# BPF.net
KiCad netlist of a schematic drawn in Altium Designer
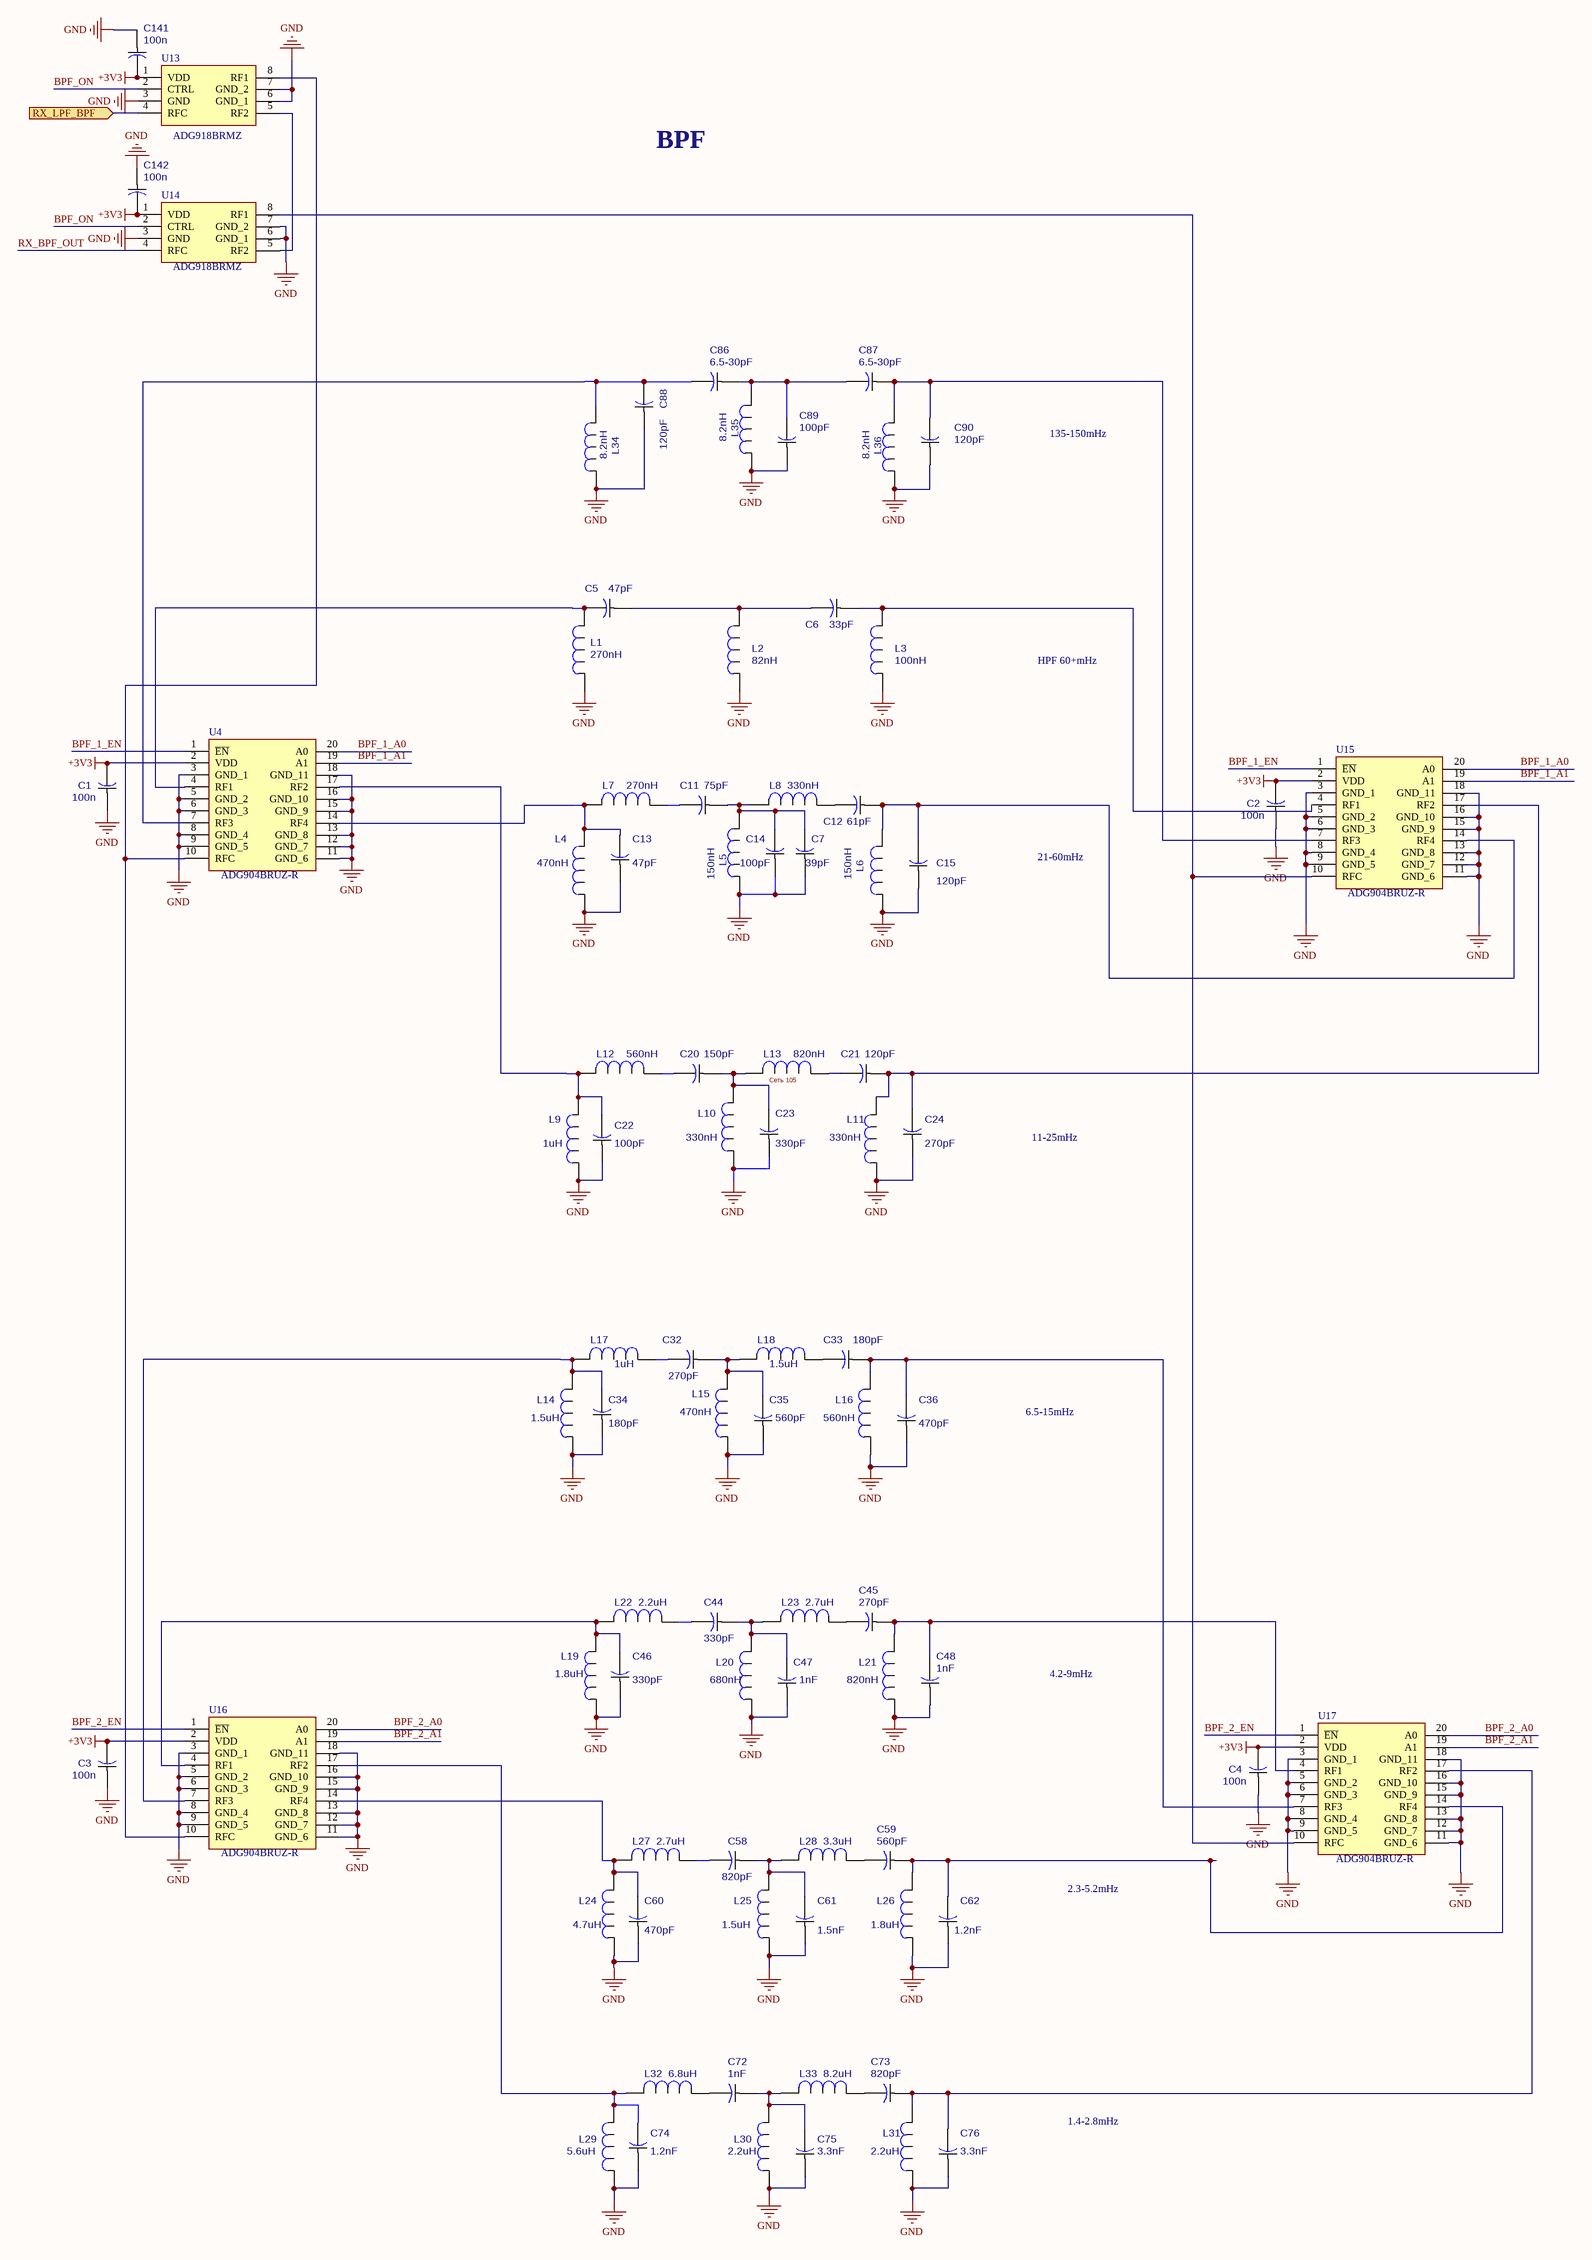
[diagram p0: BPF.SchDoc]

(export (version "E")
  (design (tool "Eeschema 10.0.6"))
  (components
    (comp (ref "C1")
      (value "100n")
      (footprint "CAP_0805")
      (description "CAP_0805")
      (libsource (lib "*") (part "CAP_0805"))
    )
    (comp (ref "C2")
      (value "100n")
      (footprint "CAP_0805")
      (description "CAP_0805")
      (libsource (lib "*") (part "CAP_0805"))
    )
    (comp (ref "C3")
      (value "100n")
      (footprint "CAP_0805")
      (description "CAP_0805")
      (libsource (lib "*") (part "CAP_0805"))
    )
    (comp (ref "C4")
      (value "100n")
      (footprint "CAP_0805")
      (description "CAP_0805")
      (libsource (lib "*") (part "CAP_0805"))
    )
    (comp (ref "C5")
      (value "47pF")
      (footprint "CAP_0805")
      (description "CAP_0805")
      (libsource (lib "*") (part "CAP_0805"))
    )
    (comp (ref "C6")
      (value "33pF")
      (footprint "CAP_0805")
      (description "CAP_0805")
      (libsource (lib "*") (part "CAP_0805"))
    )
    (comp (ref "C7")
      (value "39pF")
      (footprint "CAP_0805")
      (description "CAP_0805")
      (libsource (lib "*") (part "CAP_0805"))
    )
    (comp (ref "C11")
      (value "75pF")
      (footprint "CAP_0805")
      (description "CAP_0805")
      (libsource (lib "*") (part "CAP_0805"))
    )
    (comp (ref "C12")
      (value "61pF")
      (footprint "CAP_0805")
      (description "CAP_0805")
      (libsource (lib "*") (part "CAP_0805"))
    )
    (comp (ref "C13")
      (value "47pF")
      (footprint "CAP_0805")
      (description "CAP_0805")
      (libsource (lib "*") (part "CAP_0805"))
    )
    (comp (ref "C14")
      (value "100pF")
      (footprint "CAP_0805")
      (description "CAP_0805")
      (libsource (lib "*") (part "CAP_0805"))
    )
    (comp (ref "C15")
      (value "120pF")
      (footprint "CAP_0805")
      (description "CAP_0805")
      (libsource (lib "*") (part "CAP_0805"))
    )
    (comp (ref "C20")
      (value "150pF")
      (footprint "CAP_0805")
      (description "CAP_0805")
      (libsource (lib "*") (part "CAP_0805"))
    )
    (comp (ref "C21")
      (value "120pF")
      (footprint "CAP_0805")
      (description "CAP_0805")
      (libsource (lib "*") (part "CAP_0805"))
    )
    (comp (ref "C22")
      (value "100pF")
      (footprint "CAP_0805")
      (description "CAP_0805")
      (libsource (lib "*") (part "CAP_0805"))
    )
    (comp (ref "C23")
      (value "330pF")
      (footprint "CAP_0805")
      (description "CAP_0805")
      (libsource (lib "*") (part "CAP_0805"))
    )
    (comp (ref "C24")
      (value "270pF")
      (footprint "CAP_0805")
      (description "CAP_0805")
      (libsource (lib "*") (part "CAP_0805"))
    )
    (comp (ref "C32")
      (value "270pF")
      (footprint "CAP_0805")
      (description "CAP_0805")
      (libsource (lib "*") (part "CAP_0805"))
    )
    (comp (ref "C33")
      (value "180pF")
      (footprint "CAP_0805")
      (description "CAP_0805")
      (libsource (lib "*") (part "CAP_0805"))
    )
    (comp (ref "C34")
      (value "180pF")
      (footprint "CAP_0805")
      (description "CAP_0805")
      (libsource (lib "*") (part "CAP_0805"))
    )
    (comp (ref "C35")
      (value "560pF")
      (footprint "CAP_0805")
      (description "CAP_0805")
      (libsource (lib "*") (part "CAP_0805"))
    )
    (comp (ref "C36")
      (value "470pF")
      (footprint "CAP_0805")
      (description "CAP_0805")
      (libsource (lib "*") (part "CAP_0805"))
    )
    (comp (ref "C44")
      (value "330pF")
      (footprint "CAP_0805")
      (description "CAP_0805")
      (libsource (lib "*") (part "CAP_0805"))
    )
    (comp (ref "C45")
      (value "270pF")
      (footprint "CAP_0805")
      (description "CAP_0805")
      (fields (field (name "Comment") "51pF"))
      (libsource (lib "*") (part "CAP_0805"))
    )
    (comp (ref "C46")
      (value "330pF")
      (footprint "CAP_0805")
      (description "CAP_0805")
      (libsource (lib "*") (part "CAP_0805"))
    )
    (comp (ref "C47")
      (value "1nF")
      (footprint "CAP_0805")
      (description "CAP_0805")
      (libsource (lib "*") (part "CAP_0805"))
    )
    (comp (ref "C48")
      (value "1nF")
      (footprint "CAP_0805")
      (description "CAP_0805")
      (libsource (lib "*") (part "CAP_0805"))
    )
    (comp (ref "C58")
      (value "820pF")
      (footprint "CAP_0805")
      (description "CAP_0805")
      (libsource (lib "*") (part "CAP_0805"))
    )
    (comp (ref "C59")
      (value "560pF")
      (footprint "CAP_0805")
      (description "CAP_0805")
      (fields (field (name "Comment") "680pF"))
      (libsource (lib "*") (part "CAP_0805"))
    )
    (comp (ref "C60")
      (value "470pF")
      (footprint "CAP_0805")
      (description "CAP_0805")
      (libsource (lib "*") (part "CAP_0805"))
    )
    (comp (ref "C61")
      (value "1.5nF")
      (footprint "CAP_0805")
      (description "CAP_0805")
      (libsource (lib "*") (part "CAP_0805"))
    )
    (comp (ref "C62")
      (value "1.2nF")
      (footprint "CAP_0805")
      (description "CAP_0805")
      (libsource (lib "*") (part "CAP_0805"))
    )
    (comp (ref "C72")
      (value "1nF")
      (footprint "CAP_0805")
      (description "CAP_0805")
      (libsource (lib "*") (part "CAP_0805"))
    )
    (comp (ref "C73")
      (value "820pF")
      (footprint "CAP_0805")
      (description "CAP_0805")
      (libsource (lib "*") (part "CAP_0805"))
    )
    (comp (ref "C74")
      (value "1.2nF")
      (footprint "CAP_0805")
      (description "CAP_0805")
      (libsource (lib "*") (part "CAP_0805"))
    )
    (comp (ref "C75")
      (value "3.3nF")
      (footprint "CAP_0805")
      (description "CAP_0805")
      (libsource (lib "*") (part "CAP_0805"))
    )
    (comp (ref "C76")
      (value "3.3nF")
      (footprint "CAP_0805")
      (description "CAP_0805")
      (libsource (lib "*") (part "CAP_0805"))
    )
    (comp (ref "C86")
      (value "6.5-30pF")
      (footprint "5025[2010]")
      (description "TZC3P300A110")
      (libsource (lib "*") (part "CAP_0805"))
    )
    (comp (ref "C87")
      (value "6.5-30pF")
      (footprint "5025[2010]")
      (description "TZC3P300A110")
      (libsource (lib "*") (part "CAP_0805"))
    )
    (comp (ref "C88")
      (value "120pF")
      (footprint "CAP_0805")
      (description "CAP_0805")
      (libsource (lib "*") (part "CAP_0805"))
    )
    (comp (ref "C89")
      (value "100pF")
      (footprint "CAP_0805")
      (description "CAP_0805")
      (libsource (lib "*") (part "CAP_0805"))
    )
    (comp (ref "C90")
      (value "120pF")
      (footprint "CAP_0805")
      (description "CAP_0805")
      (libsource (lib "*") (part "CAP_0805"))
    )
    (comp (ref "C141")
      (value "100n")
      (footprint "CAP_0805")
      (description "CAP_0805")
      (libsource (lib "*") (part "CAP_0805"))
    )
    (comp (ref "C142")
      (value "100n")
      (footprint "CAP_0805")
      (description "CAP_0805")
      (libsource (lib "*") (part "CAP_0805"))
    )
    (comp (ref "L1")
      (value "270nH")
      (footprint "IND_0805")
      (description "IND_0805")
      (libsource (lib "*") (part "IND_0805"))
    )
    (comp (ref "L2")
      (value "82nH")
      (footprint "IND_0805")
      (description "IND_0805")
      (libsource (lib "*") (part "IND_0805"))
    )
    (comp (ref "L3")
      (value "100nH")
      (footprint "IND_0805")
      (description "IND_0805")
      (libsource (lib "*") (part "IND_0805"))
    )
    (comp (ref "L4")
      (value "470nH")
      (footprint "IND_0805")
      (description "IND_0805")
      (libsource (lib "*") (part "IND_0805"))
    )
    (comp (ref "L5")
      (value "150nH")
      (footprint "IND_0805")
      (description "IND_0805")
      (libsource (lib "*") (part "IND_0805"))
    )
    (comp (ref "L6")
      (value "150nH")
      (footprint "IND_0805")
      (description "IND_0805")
      (libsource (lib "*") (part "IND_0805"))
    )
    (comp (ref "L7")
      (value "270nH")
      (footprint "IND_0805")
      (description "IND_0805")
      (libsource (lib "*") (part "IND_0805"))
    )
    (comp (ref "L8")
      (value "330nH")
      (footprint "IND_0805")
      (description "IND_0805")
      (libsource (lib "*") (part "IND_0805"))
    )
    (comp (ref "L9")
      (value "1uH")
      (footprint "IND_0805")
      (description "IND_0805")
      (libsource (lib "*") (part "IND_0805"))
    )
    (comp (ref "L10")
      (value "330nH")
      (footprint "IND_0805")
      (description "IND_0805")
      (libsource (lib "*") (part "IND_0805"))
    )
    (comp (ref "L11")
      (value "330nH")
      (footprint "IND_0805")
      (description "IND_0805")
      (libsource (lib "*") (part "IND_0805"))
    )
    (comp (ref "L12")
      (value "560nH")
      (footprint "IND_0805")
      (description "IND_0805")
      (libsource (lib "*") (part "IND_0805"))
    )
    (comp (ref "L13")
      (value "820nH")
      (footprint "IND_0805")
      (description "IND_0805")
      (libsource (lib "*") (part "IND_0805"))
    )
    (comp (ref "L14")
      (value "1.5uH")
      (footprint "IND_0805")
      (description "IND_0805")
      (libsource (lib "*") (part "IND_0805"))
    )
    (comp (ref "L15")
      (value "470nH")
      (footprint "IND_0805")
      (description "IND_0805")
      (libsource (lib "*") (part "IND_0805"))
    )
    (comp (ref "L16")
      (value "560nH")
      (footprint "IND_0805")
      (description "IND_0805")
      (libsource (lib "*") (part "IND_0805"))
    )
    (comp (ref "L17")
      (value "1uH")
      (footprint "IND_0805")
      (description "IND_0805")
      (libsource (lib "*") (part "IND_0805"))
    )
    (comp (ref "L18")
      (value "1.5uH")
      (footprint "IND_0805")
      (description "IND_0805")
      (libsource (lib "*") (part "IND_0805"))
    )
    (comp (ref "L19")
      (value "1.8uH")
      (footprint "IND_0805")
      (description "IND_0805")
      (libsource (lib "*") (part "IND_0805"))
    )
    (comp (ref "L20")
      (value "680nH")
      (footprint "IND_0805")
      (description "IND_0805")
      (libsource (lib "*") (part "IND_0805"))
    )
    (comp (ref "L21")
      (value "820nH")
      (footprint "IND_0805")
      (description "IND_0805")
      (libsource (lib "*") (part "IND_0805"))
    )
    (comp (ref "L22")
      (value "2.2uH")
      (footprint "IND_0805")
      (description "IND_0805")
      (libsource (lib "*") (part "IND_0805"))
    )
    (comp (ref "L23")
      (value "2.7uH")
      (footprint "IND_0805")
      (description "IND_0805")
      (libsource (lib "*") (part "IND_0805"))
    )
    (comp (ref "L24")
      (value "4.7uH")
      (footprint "IND_0805")
      (description "IND_0805")
      (libsource (lib "*") (part "IND_0805"))
    )
    (comp (ref "L25")
      (value "1.5uH")
      (footprint "IND_0805")
      (description "IND_0805")
      (libsource (lib "*") (part "IND_0805"))
    )
    (comp (ref "L26")
      (value "1.8uH")
      (footprint "IND_0805")
      (description "IND_0805")
      (libsource (lib "*") (part "IND_0805"))
    )
    (comp (ref "L27")
      (value "2.7uH")
      (footprint "IND_0805")
      (description "IND_0805")
      (libsource (lib "*") (part "IND_0805"))
    )
    (comp (ref "L28")
      (value "3.3uH")
      (footprint "IND_0805")
      (description "IND_0805")
      (libsource (lib "*") (part "IND_0805"))
    )
    (comp (ref "L29")
      (value "5.6uH")
      (footprint "IND_0805")
      (description "IND_0805")
      (libsource (lib "*") (part "IND_0805"))
    )
    (comp (ref "L30")
      (value "2.2uH")
      (footprint "IND_0805")
      (description "IND_0805")
      (libsource (lib "*") (part "IND_0805"))
    )
    (comp (ref "L31")
      (value "2.2uH")
      (footprint "IND_0805")
      (description "IND_0805")
      (libsource (lib "*") (part "IND_0805"))
    )
    (comp (ref "L32")
      (value "6.8uH")
      (footprint "IND_0805")
      (description "IND_0805")
      (libsource (lib "*") (part "IND_0805"))
    )
    (comp (ref "L33")
      (value "8.2uH")
      (footprint "IND_0805")
      (description "IND_0805")
      (libsource (lib "*") (part "IND_0805"))
    )
    (comp (ref "L34")
      (value "8.2nH")
      (footprint "IND_0805")
      (description "IND_0805")
      (libsource (lib "*") (part "IND_0805"))
    )
    (comp (ref "L35")
      (value "8.2nH")
      (footprint "IND_0805")
      (description "IND_0805")
      (libsource (lib "*") (part "IND_0805"))
    )
    (comp (ref "L36")
      (value "8.2nH")
      (footprint "IND_0805")
      (description "IND_0805")
      (libsource (lib "*") (part "IND_0805"))
    )
    (comp (ref "U4")
      (value "ADG904BRUZ-R")
      (footprint "SamacSys:SOP65P640X120-20N")
      (description "Integrated Circuit")
      (fields
        (field (name "MOUSER PART NUMBER") "584-ADG904BRUZ-R")
        (field (name "RS PART NUMBER") "5385019P")
      )
      (libsource (lib "*") (part "ADG904BRUZ-R"))
    )
    (comp (ref "U13")
      (value "ADG918BRMZ")
      (footprint "SamacSys:SOP65P490X110-8N")
      (description "Integrated Circuit")
      (fields (field (name "MOUSER PART NUMBER") "584-ADG918BRMZ") (field (name "RS PART NUMBER") "4969212P"))
      (libsource (lib "*") (part "ADG918BRMZ"))
    )
    (comp (ref "U14")
      (value "ADG918BRMZ")
      (footprint "SamacSys:SOP65P490X110-8N")
      (description "Integrated Circuit")
      (fields (field (name "MOUSER PART NUMBER") "584-ADG918BRMZ") (field (name "RS PART NUMBER") "4969212P"))
      (libsource (lib "*") (part "ADG918BRMZ"))
    )
    (comp (ref "U15")
      (value "ADG904BRUZ-R")
      (footprint "SamacSys:SOP65P640X120-20N")
      (description "Integrated Circuit")
      (fields
        (field (name "MOUSER PART NUMBER") "584-ADG904BRUZ-R")
        (field (name "RS PART NUMBER") "5385019P")
      )
      (libsource (lib "*") (part "ADG904BRUZ-R"))
    )
    (comp (ref "U16")
      (value "ADG904BRUZ-R")
      (footprint "SamacSys:SOP65P640X120-20N")
      (description "Integrated Circuit")
      (fields
        (field (name "MOUSER PART NUMBER") "584-ADG904BRUZ-R")
        (field (name "RS PART NUMBER") "5385019P")
      )
      (libsource (lib "*") (part "ADG904BRUZ-R"))
    )
    (comp (ref "U17")
      (value "ADG904BRUZ-R")
      (footprint "SamacSys:SOP65P640X120-20N")
      (description "Integrated Circuit")
      (fields
        (field (name "MOUSER PART NUMBER") "584-ADG904BRUZ-R")
        (field (name "RS PART NUMBER") "5385019P")
      )
      (libsource (lib "*") (part "ADG904BRUZ-R"))
    )
  )
  (nets
    (net (code "1") (name "+3V3") (class "Default")
      (node (ref "C1") (pin "2") (pinfunction "2_2") (pintype "passive"))
      (node (ref "C141") (pin "2") (pinfunction "2_2") (pintype "passive"))
      (node (ref "C142") (pin "2") (pinfunction "2_2") (pintype "passive"))
      (node (ref "C2") (pin "2") (pinfunction "2_2") (pintype "passive"))
      (node (ref "C3") (pin "2") (pinfunction "2_2") (pintype "passive"))
      (node (ref "C4") (pin "2") (pinfunction "2_2") (pintype "passive"))
      (node (ref "U13") (pin "1") (pinfunction "VDD_1") (pintype "power_in"))
      (node (ref "U14") (pin "1") (pinfunction "VDD_1") (pintype "power_in"))
      (node (ref "U15") (pin "2") (pinfunction "VDD_2") (pintype "passive"))
      (node (ref "U16") (pin "2") (pinfunction "VDD_2") (pintype "passive"))
      (node (ref "U17") (pin "2") (pinfunction "VDD_2") (pintype "passive"))
      (node (ref "U4") (pin "2") (pinfunction "VDD_2") (pintype "passive"))
    )
    (net (code "2") (name "/BPF_1_A0") (class "Default")
      (node (ref "U15") (pin "20") (pinfunction "A0_20") (pintype "passive"))
      (node (ref "U4") (pin "20") (pinfunction "A0_20") (pintype "passive"))
    )
    (net (code "3") (name "/BPF_1_A1") (class "Default")
      (node (ref "U15") (pin "19") (pinfunction "A1_19") (pintype "passive"))
      (node (ref "U4") (pin "19") (pinfunction "A1_19") (pintype "passive"))
    )
    (net (code "4") (name "/BPF_1_EN") (class "Default")
      (node (ref "U15") (pin "1") (pinfunction "~{EN}_1") (pintype "passive"))
      (node (ref "U4") (pin "1") (pinfunction "~{EN}_1") (pintype "passive"))
    )
    (net (code "5") (name "/BPF_2_A0") (class "Default")
      (node (ref "U16") (pin "20") (pinfunction "A0_20") (pintype "passive"))
      (node (ref "U17") (pin "20") (pinfunction "A0_20") (pintype "passive"))
    )
    (net (code "6") (name "/BPF_2_A1") (class "Default")
      (node (ref "U16") (pin "19") (pinfunction "A1_19") (pintype "passive"))
      (node (ref "U17") (pin "19") (pinfunction "A1_19") (pintype "passive"))
    )
    (net (code "7") (name "/BPF_2_EN") (class "Default")
      (node (ref "U16") (pin "1") (pinfunction "~{EN}_1") (pintype "passive"))
      (node (ref "U17") (pin "1") (pinfunction "~{EN}_1") (pintype "passive"))
    )
    (net (code "8") (name "/BPF_ON") (class "Default")
      (node (ref "U13") (pin "2") (pinfunction "CTRL_2") (pintype "passive"))
      (node (ref "U14") (pin "2") (pinfunction "CTRL_2") (pintype "passive"))
    )
    (net (code "9") (name "/RX_BPF_OUT") (class "Default")
      (node (ref "U14") (pin "4") (pinfunction "RFC_4") (pintype "passive"))
    )
    (net (code "10") (name "/RX_LPF_BPF") (class "Default")
      (node (ref "U13") (pin "4") (pinfunction "RFC_4") (pintype "passive"))
    )
    (net (code "11") (name "/Сеть 105") (class "Default")
      (node (ref "C20") (pin "1") (pinfunction "1_1") (pintype "passive"))
      (node (ref "C23") (pin "2") (pinfunction "2_2") (pintype "passive"))
      (node (ref "L10") (pin "2") (pinfunction "2_2") (pintype "passive"))
      (node (ref "L13") (pin "1") (pinfunction "1_1") (pintype "passive"))
    )
    (net (code "12") (name "GND") (class "Default")
      (node (ref "C1") (pin "1") (pinfunction "1_1") (pintype "passive"))
      (node (ref "C13") (pin "1") (pinfunction "1_1") (pintype "passive"))
      (node (ref "C14") (pin "1") (pinfunction "1_1") (pintype "passive"))
      (node (ref "C141") (pin "1") (pinfunction "1_1") (pintype "passive"))
      (node (ref "C142") (pin "1") (pinfunction "1_1") (pintype "passive"))
      (node (ref "C15") (pin "1") (pinfunction "1_1") (pintype "passive"))
      (node (ref "C2") (pin "1") (pinfunction "1_1") (pintype "passive"))
      (node (ref "C22") (pin "1") (pinfunction "1_1") (pintype "passive"))
      (node (ref "C23") (pin "1") (pinfunction "1_1") (pintype "passive"))
      (node (ref "C24") (pin "1") (pinfunction "1_1") (pintype "passive"))
      (node (ref "C3") (pin "1") (pinfunction "1_1") (pintype "passive"))
      (node (ref "C34") (pin "1") (pinfunction "1_1") (pintype "passive"))
      (node (ref "C35") (pin "1") (pinfunction "1_1") (pintype "passive"))
      (node (ref "C36") (pin "1") (pinfunction "1_1") (pintype "passive"))
      (node (ref "C4") (pin "1") (pinfunction "1_1") (pintype "passive"))
      (node (ref "C46") (pin "1") (pinfunction "1_1") (pintype "passive"))
      (node (ref "C47") (pin "1") (pinfunction "1_1") (pintype "passive"))
      (node (ref "C48") (pin "1") (pinfunction "1_1") (pintype "passive"))
      (node (ref "C60") (pin "1") (pinfunction "1_1") (pintype "passive"))
      (node (ref "C61") (pin "1") (pinfunction "1_1") (pintype "passive"))
      (node (ref "C62") (pin "1") (pinfunction "1_1") (pintype "passive"))
      (node (ref "C7") (pin "1") (pinfunction "1_1") (pintype "passive"))
      (node (ref "C74") (pin "1") (pinfunction "1_1") (pintype "passive"))
      (node (ref "C75") (pin "1") (pinfunction "1_1") (pintype "passive"))
      (node (ref "C76") (pin "1") (pinfunction "1_1") (pintype "passive"))
      (node (ref "C88") (pin "1") (pinfunction "1_1") (pintype "passive"))
      (node (ref "C89") (pin "1") (pinfunction "1_1") (pintype "passive"))
      (node (ref "C90") (pin "1") (pinfunction "1_1") (pintype "passive"))
      (node (ref "L1") (pin "1") (pinfunction "1_1") (pintype "passive"))
      (node (ref "L10") (pin "1") (pinfunction "1_1") (pintype "passive"))
      (node (ref "L11") (pin "1") (pinfunction "1_1") (pintype "passive"))
      (node (ref "L14") (pin "1") (pinfunction "1_1") (pintype "passive"))
      (node (ref "L15") (pin "1") (pinfunction "1_1") (pintype "passive"))
      (node (ref "L16") (pin "1") (pinfunction "1_1") (pintype "passive"))
      (node (ref "L19") (pin "1") (pinfunction "1_1") (pintype "passive"))
      (node (ref "L2") (pin "1") (pinfunction "1_1") (pintype "passive"))
      (node (ref "L20") (pin "1") (pinfunction "1_1") (pintype "passive"))
      (node (ref "L21") (pin "1") (pinfunction "1_1") (pintype "passive"))
      (node (ref "L24") (pin "1") (pinfunction "1_1") (pintype "passive"))
      (node (ref "L25") (pin "1") (pinfunction "1_1") (pintype "passive"))
      (node (ref "L26") (pin "1") (pinfunction "1_1") (pintype "passive"))
      (node (ref "L29") (pin "1") (pinfunction "1_1") (pintype "passive"))
      (node (ref "L3") (pin "1") (pinfunction "1_1") (pintype "passive"))
      (node (ref "L30") (pin "1") (pinfunction "1_1") (pintype "passive"))
      (node (ref "L31") (pin "1") (pinfunction "1_1") (pintype "passive"))
      (node (ref "L34") (pin "1") (pinfunction "1_1") (pintype "passive"))
      (node (ref "L35") (pin "1") (pinfunction "1_1") (pintype "passive"))
      (node (ref "L36") (pin "1") (pinfunction "1_1") (pintype "passive"))
      (node (ref "L4") (pin "1") (pinfunction "1_1") (pintype "passive"))
      (node (ref "L5") (pin "1") (pinfunction "1_1") (pintype "passive"))
      (node (ref "L6") (pin "1") (pinfunction "1_1") (pintype "passive"))
      (node (ref "L9") (pin "1") (pinfunction "1_1") (pintype "passive"))
      (node (ref "U13") (pin "3") (pinfunction "GND_3") (pintype "power_in"))
      (node (ref "U13") (pin "6") (pinfunction "GND_1_6") (pintype "power_in"))
      (node (ref "U13") (pin "7") (pinfunction "GND_2_7") (pintype "power_in"))
      (node (ref "U14") (pin "3") (pinfunction "GND_3") (pintype "power_in"))
      (node (ref "U14") (pin "6") (pinfunction "GND_1_6") (pintype "power_in"))
      (node (ref "U14") (pin "7") (pinfunction "GND_2_7") (pintype "power_in"))
      (node (ref "U15") (pin "11") (pinfunction "GND_6_11") (pintype "passive"))
      (node (ref "U15") (pin "12") (pinfunction "GND_7_12") (pintype "passive"))
      (node (ref "U15") (pin "13") (pinfunction "GND_8_13") (pintype "passive"))
      (node (ref "U15") (pin "15") (pinfunction "GND_9_15") (pintype "passive"))
      (node (ref "U15") (pin "16") (pinfunction "GND_10_16") (pintype "passive"))
      (node (ref "U15") (pin "18") (pinfunction "GND_11_18") (pintype "passive"))
      (node (ref "U15") (pin "3") (pinfunction "GND_1_3") (pintype "passive"))
      (node (ref "U15") (pin "5") (pinfunction "GND_2_5") (pintype "passive"))
      (node (ref "U15") (pin "6") (pinfunction "GND_3_6") (pintype "passive"))
      (node (ref "U15") (pin "8") (pinfunction "GND_4_8") (pintype "passive"))
      (node (ref "U15") (pin "9") (pinfunction "GND_5_9") (pintype "passive"))
      (node (ref "U16") (pin "11") (pinfunction "GND_6_11") (pintype "passive"))
      (node (ref "U16") (pin "12") (pinfunction "GND_7_12") (pintype "passive"))
      (node (ref "U16") (pin "13") (pinfunction "GND_8_13") (pintype "passive"))
      (node (ref "U16") (pin "15") (pinfunction "GND_9_15") (pintype "passive"))
      (node (ref "U16") (pin "16") (pinfunction "GND_10_16") (pintype "passive"))
      (node (ref "U16") (pin "18") (pinfunction "GND_11_18") (pintype "passive"))
      (node (ref "U16") (pin "3") (pinfunction "GND_1_3") (pintype "passive"))
      (node (ref "U16") (pin "5") (pinfunction "GND_2_5") (pintype "passive"))
      (node (ref "U16") (pin "6") (pinfunction "GND_3_6") (pintype "passive"))
      (node (ref "U16") (pin "8") (pinfunction "GND_4_8") (pintype "passive"))
      (node (ref "U16") (pin "9") (pinfunction "GND_5_9") (pintype "passive"))
      (node (ref "U17") (pin "11") (pinfunction "GND_6_11") (pintype "passive"))
      (node (ref "U17") (pin "12") (pinfunction "GND_7_12") (pintype "passive"))
      (node (ref "U17") (pin "13") (pinfunction "GND_8_13") (pintype "passive"))
      (node (ref "U17") (pin "15") (pinfunction "GND_9_15") (pintype "passive"))
      (node (ref "U17") (pin "16") (pinfunction "GND_10_16") (pintype "passive"))
      (node (ref "U17") (pin "18") (pinfunction "GND_11_18") (pintype "passive"))
      (node (ref "U17") (pin "3") (pinfunction "GND_1_3") (pintype "passive"))
      (node (ref "U17") (pin "5") (pinfunction "GND_2_5") (pintype "passive"))
      (node (ref "U17") (pin "6") (pinfunction "GND_3_6") (pintype "passive"))
      (node (ref "U17") (pin "8") (pinfunction "GND_4_8") (pintype "passive"))
      (node (ref "U17") (pin "9") (pinfunction "GND_5_9") (pintype "passive"))
      (node (ref "U4") (pin "11") (pinfunction "GND_6_11") (pintype "passive"))
      (node (ref "U4") (pin "12") (pinfunction "GND_7_12") (pintype "passive"))
      (node (ref "U4") (pin "13") (pinfunction "GND_8_13") (pintype "passive"))
      (node (ref "U4") (pin "15") (pinfunction "GND_9_15") (pintype "passive"))
      (node (ref "U4") (pin "16") (pinfunction "GND_10_16") (pintype "passive"))
      (node (ref "U4") (pin "18") (pinfunction "GND_11_18") (pintype "passive"))
      (node (ref "U4") (pin "3") (pinfunction "GND_1_3") (pintype "passive"))
      (node (ref "U4") (pin "5") (pinfunction "GND_2_5") (pintype "passive"))
      (node (ref "U4") (pin "6") (pinfunction "GND_3_6") (pintype "passive"))
      (node (ref "U4") (pin "8") (pinfunction "GND_4_8") (pintype "passive"))
      (node (ref "U4") (pin "9") (pinfunction "GND_5_9") (pintype "passive"))
    )
    (net (code "13") (name "Net-(C5-Pad1)") (class "Default")
      (node (ref "C5") (pin "1") (pinfunction "1_1") (pintype "passive"))
      (node (ref "C6") (pin "2") (pinfunction "2_2") (pintype "passive"))
      (node (ref "L2") (pin "2") (pinfunction "2_2") (pintype "passive"))
    )
    (net (code "14") (name "Net-(C11-Pad1)") (class "Default")
      (node (ref "C11") (pin "1") (pinfunction "1_1") (pintype "passive"))
      (node (ref "C14") (pin "2") (pinfunction "2_2") (pintype "passive"))
      (node (ref "C7") (pin "2") (pinfunction "2_2") (pintype "passive"))
      (node (ref "L5") (pin "2") (pinfunction "2_2") (pintype "passive"))
      (node (ref "L8") (pin "1") (pinfunction "1_1") (pintype "passive"))
    )
    (net (code "15") (name "Net-(C11-Pad2)") (class "Default")
      (node (ref "C11") (pin "2") (pinfunction "2_2") (pintype "passive"))
      (node (ref "L7") (pin "2") (pinfunction "2_2") (pintype "passive"))
    )
    (net (code "16") (name "Net-(C12-Pad2)") (class "Default")
      (node (ref "C12") (pin "2") (pinfunction "2_2") (pintype "passive"))
      (node (ref "L8") (pin "2") (pinfunction "2_2") (pintype "passive"))
    )
    (net (code "17") (name "Net-(C20-Pad2)") (class "Default")
      (node (ref "C20") (pin "2") (pinfunction "2_2") (pintype "passive"))
      (node (ref "L12") (pin "2") (pinfunction "2_2") (pintype "passive"))
    )
    (net (code "18") (name "Net-(C21-Pad2)") (class "Default")
      (node (ref "C21") (pin "2") (pinfunction "2_2") (pintype "passive"))
      (node (ref "L13") (pin "2") (pinfunction "2_2") (pintype "passive"))
    )
    (net (code "19") (name "Net-(C32-Pad1)") (class "Default")
      (node (ref "C32") (pin "1") (pinfunction "1_1") (pintype "passive"))
      (node (ref "C35") (pin "2") (pinfunction "2_2") (pintype "passive"))
      (node (ref "L15") (pin "2") (pinfunction "2_2") (pintype "passive"))
      (node (ref "L18") (pin "1") (pinfunction "1_1") (pintype "passive"))
    )
    (net (code "20") (name "Net-(C32-Pad2)") (class "Default")
      (node (ref "C32") (pin "2") (pinfunction "2_2") (pintype "passive"))
      (node (ref "L17") (pin "2") (pinfunction "2_2") (pintype "passive"))
    )
    (net (code "21") (name "Net-(C33-Pad2)") (class "Default")
      (node (ref "C33") (pin "2") (pinfunction "2_2") (pintype "passive"))
      (node (ref "L18") (pin "2") (pinfunction "2_2") (pintype "passive"))
    )
    (net (code "22") (name "Net-(C44-Pad1)") (class "Default")
      (node (ref "C44") (pin "1") (pinfunction "1_1") (pintype "passive"))
      (node (ref "C47") (pin "2") (pinfunction "2_2") (pintype "passive"))
      (node (ref "L20") (pin "2") (pinfunction "2_2") (pintype "passive"))
      (node (ref "L23") (pin "1") (pinfunction "1_1") (pintype "passive"))
    )
    (net (code "23") (name "Net-(C44-Pad2)") (class "Default")
      (node (ref "C44") (pin "2") (pinfunction "2_2") (pintype "passive"))
      (node (ref "L22") (pin "2") (pinfunction "2_2") (pintype "passive"))
    )
    (net (code "24") (name "Net-(C45-Pad2)") (class "Default")
      (node (ref "C45") (pin "2") (pinfunction "2_2") (pintype "passive"))
      (node (ref "L23") (pin "2") (pinfunction "2_2") (pintype "passive"))
    )
    (net (code "25") (name "Net-(C58-Pad1)") (class "Default")
      (node (ref "C58") (pin "1") (pinfunction "1_1") (pintype "passive"))
      (node (ref "C61") (pin "2") (pinfunction "2_2") (pintype "passive"))
      (node (ref "L25") (pin "2") (pinfunction "2_2") (pintype "passive"))
      (node (ref "L28") (pin "1") (pinfunction "1_1") (pintype "passive"))
    )
    (net (code "26") (name "Net-(C58-Pad2)") (class "Default")
      (node (ref "C58") (pin "2") (pinfunction "2_2") (pintype "passive"))
      (node (ref "L27") (pin "2") (pinfunction "2_2") (pintype "passive"))
    )
    (net (code "27") (name "Net-(C59-Pad2)") (class "Default")
      (node (ref "C59") (pin "2") (pinfunction "2_2") (pintype "passive"))
      (node (ref "L28") (pin "2") (pinfunction "2_2") (pintype "passive"))
    )
    (net (code "28") (name "Net-(C72-Pad1)") (class "Default")
      (node (ref "C72") (pin "1") (pinfunction "1_1") (pintype "passive"))
      (node (ref "C75") (pin "2") (pinfunction "2_2") (pintype "passive"))
      (node (ref "L30") (pin "2") (pinfunction "2_2") (pintype "passive"))
      (node (ref "L33") (pin "1") (pinfunction "1_1") (pintype "passive"))
    )
    (net (code "29") (name "Net-(C72-Pad2)") (class "Default")
      (node (ref "C72") (pin "2") (pinfunction "2_2") (pintype "passive"))
      (node (ref "L32") (pin "2") (pinfunction "2_2") (pintype "passive"))
    )
    (net (code "30") (name "Net-(C73-Pad2)") (class "Default")
      (node (ref "C73") (pin "2") (pinfunction "2_2") (pintype "passive"))
      (node (ref "L33") (pin "2") (pinfunction "2_2") (pintype "passive"))
    )
    (net (code "31") (name "Net-(C86-Pad1)") (class "Default")
      (node (ref "C86") (pin "1") (pinfunction "1_1") (pintype "passive"))
      (node (ref "C87") (pin "2") (pinfunction "2_2") (pintype "passive"))
      (node (ref "C89") (pin "2") (pinfunction "2_2") (pintype "passive"))
      (node (ref "L35") (pin "2") (pinfunction "2_2") (pintype "passive"))
    )
    (net (code "32") (name "Net-(U4-RF1)") (class "Default")
      (node (ref "C5") (pin "2") (pinfunction "2_2") (pintype "passive"))
      (node (ref "L1") (pin "2") (pinfunction "2_2") (pintype "passive"))
      (node (ref "U4") (pin "4") (pinfunction "RF1_4") (pintype "passive"))
    )
    (net (code "33") (name "Net-(U4-RF2)") (class "Default")
      (node (ref "C22") (pin "2") (pinfunction "2_2") (pintype "passive"))
      (node (ref "L12") (pin "1") (pinfunction "1_1") (pintype "passive"))
      (node (ref "L9") (pin "2") (pinfunction "2_2") (pintype "passive"))
      (node (ref "U4") (pin "17") (pinfunction "RF2_17") (pintype "passive"))
    )
    (net (code "34") (name "Net-(U4-RF3)") (class "Default")
      (node (ref "C86") (pin "2") (pinfunction "2_2") (pintype "passive"))
      (node (ref "C88") (pin "2") (pinfunction "2_2") (pintype "passive"))
      (node (ref "L34") (pin "2") (pinfunction "2_2") (pintype "passive"))
      (node (ref "U4") (pin "7") (pinfunction "RF3_7") (pintype "passive"))
    )
    (net (code "35") (name "Net-(U4-RF4)") (class "Default")
      (node (ref "C13") (pin "2") (pinfunction "2_2") (pintype "passive"))
      (node (ref "L4") (pin "2") (pinfunction "2_2") (pintype "passive"))
      (node (ref "L7") (pin "1") (pinfunction "1_1") (pintype "passive"))
      (node (ref "U4") (pin "14") (pinfunction "RF4_14") (pintype "passive"))
    )
    (net (code "36") (name "Net-(U13-RF1)") (class "Default")
      (node (ref "U13") (pin "8") (pinfunction "RF1_8") (pintype "passive"))
      (node (ref "U16") (pin "10") (pinfunction "RFC_10") (pintype "passive"))
      (node (ref "U4") (pin "10") (pinfunction "RFC_10") (pintype "passive"))
    )
    (net (code "37") (name "Net-(U13-RF2)") (class "Default")
      (node (ref "U13") (pin "5") (pinfunction "RF2_5") (pintype "passive"))
      (node (ref "U14") (pin "5") (pinfunction "RF2_5") (pintype "passive"))
    )
    (net (code "38") (name "Net-(U14-RF1)") (class "Default")
      (node (ref "U14") (pin "8") (pinfunction "RF1_8") (pintype "passive"))
      (node (ref "U15") (pin "10") (pinfunction "RFC_10") (pintype "passive"))
      (node (ref "U17") (pin "10") (pinfunction "RFC_10") (pintype "passive"))
    )
    (net (code "39") (name "Net-(U15-RF1)") (class "Default")
      (node (ref "C6") (pin "1") (pinfunction "1_1") (pintype "passive"))
      (node (ref "L3") (pin "2") (pinfunction "2_2") (pintype "passive"))
      (node (ref "U15") (pin "4") (pinfunction "RF1_4") (pintype "passive"))
    )
    (net (code "40") (name "Net-(U15-RF2)") (class "Default")
      (node (ref "C21") (pin "1") (pinfunction "1_1") (pintype "passive"))
      (node (ref "C24") (pin "2") (pinfunction "2_2") (pintype "passive"))
      (node (ref "L11") (pin "2") (pinfunction "2_2") (pintype "passive"))
      (node (ref "U15") (pin "17") (pinfunction "RF2_17") (pintype "passive"))
    )
    (net (code "41") (name "Net-(U15-RF3)") (class "Default")
      (node (ref "C87") (pin "1") (pinfunction "1_1") (pintype "passive"))
      (node (ref "C90") (pin "2") (pinfunction "2_2") (pintype "passive"))
      (node (ref "L36") (pin "2") (pinfunction "2_2") (pintype "passive"))
      (node (ref "U15") (pin "7") (pinfunction "RF3_7") (pintype "passive"))
    )
    (net (code "42") (name "Net-(U15-RF4)") (class "Default")
      (node (ref "C12") (pin "1") (pinfunction "1_1") (pintype "passive"))
      (node (ref "C15") (pin "2") (pinfunction "2_2") (pintype "passive"))
      (node (ref "L6") (pin "2") (pinfunction "2_2") (pintype "passive"))
      (node (ref "U15") (pin "14") (pinfunction "RF4_14") (pintype "passive"))
    )
    (net (code "43") (name "Net-(U16-RF1)") (class "Default")
      (node (ref "C46") (pin "2") (pinfunction "2_2") (pintype "passive"))
      (node (ref "L19") (pin "2") (pinfunction "2_2") (pintype "passive"))
      (node (ref "L22") (pin "1") (pinfunction "1_1") (pintype "passive"))
      (node (ref "U16") (pin "4") (pinfunction "RF1_4") (pintype "passive"))
    )
    (net (code "44") (name "Net-(U16-RF2)") (class "Default")
      (node (ref "C74") (pin "2") (pinfunction "2_2") (pintype "passive"))
      (node (ref "L29") (pin "2") (pinfunction "2_2") (pintype "passive"))
      (node (ref "L32") (pin "1") (pinfunction "1_1") (pintype "passive"))
      (node (ref "U16") (pin "17") (pinfunction "RF2_17") (pintype "passive"))
    )
    (net (code "45") (name "Net-(U16-RF3)") (class "Default")
      (node (ref "C34") (pin "2") (pinfunction "2_2") (pintype "passive"))
      (node (ref "L14") (pin "2") (pinfunction "2_2") (pintype "passive"))
      (node (ref "L17") (pin "1") (pinfunction "1_1") (pintype "passive"))
      (node (ref "U16") (pin "7") (pinfunction "RF3_7") (pintype "passive"))
    )
    (net (code "46") (name "Net-(U16-RF4)") (class "Default")
      (node (ref "C60") (pin "2") (pinfunction "2_2") (pintype "passive"))
      (node (ref "L24") (pin "2") (pinfunction "2_2") (pintype "passive"))
      (node (ref "L27") (pin "1") (pinfunction "1_1") (pintype "passive"))
      (node (ref "U16") (pin "14") (pinfunction "RF4_14") (pintype "passive"))
    )
    (net (code "47") (name "Net-(U17-RF1)") (class "Default")
      (node (ref "C45") (pin "1") (pinfunction "1_1") (pintype "passive"))
      (node (ref "C48") (pin "2") (pinfunction "2_2") (pintype "passive"))
      (node (ref "L21") (pin "2") (pinfunction "2_2") (pintype "passive"))
      (node (ref "U17") (pin "4") (pinfunction "RF1_4") (pintype "passive"))
    )
    (net (code "48") (name "Net-(U17-RF2)") (class "Default")
      (node (ref "C73") (pin "1") (pinfunction "1_1") (pintype "passive"))
      (node (ref "C76") (pin "2") (pinfunction "2_2") (pintype "passive"))
      (node (ref "L31") (pin "2") (pinfunction "2_2") (pintype "passive"))
      (node (ref "U17") (pin "17") (pinfunction "RF2_17") (pintype "passive"))
    )
    (net (code "49") (name "Net-(U17-RF3)") (class "Default")
      (node (ref "C33") (pin "1") (pinfunction "1_1") (pintype "passive"))
      (node (ref "C36") (pin "2") (pinfunction "2_2") (pintype "passive"))
      (node (ref "L16") (pin "2") (pinfunction "2_2") (pintype "passive"))
      (node (ref "U17") (pin "7") (pinfunction "RF3_7") (pintype "passive"))
    )
    (net (code "50") (name "Net-(U17-RF4)") (class "Default")
      (node (ref "C59") (pin "1") (pinfunction "1_1") (pintype "passive"))
      (node (ref "C62") (pin "2") (pinfunction "2_2") (pintype "passive"))
      (node (ref "L26") (pin "2") (pinfunction "2_2") (pintype "passive"))
      (node (ref "U17") (pin "14") (pinfunction "RF4_14") (pintype "passive"))
    )
  )
)
